# UART.net
KiCad netlist of a schematic drawn in Altium Designer
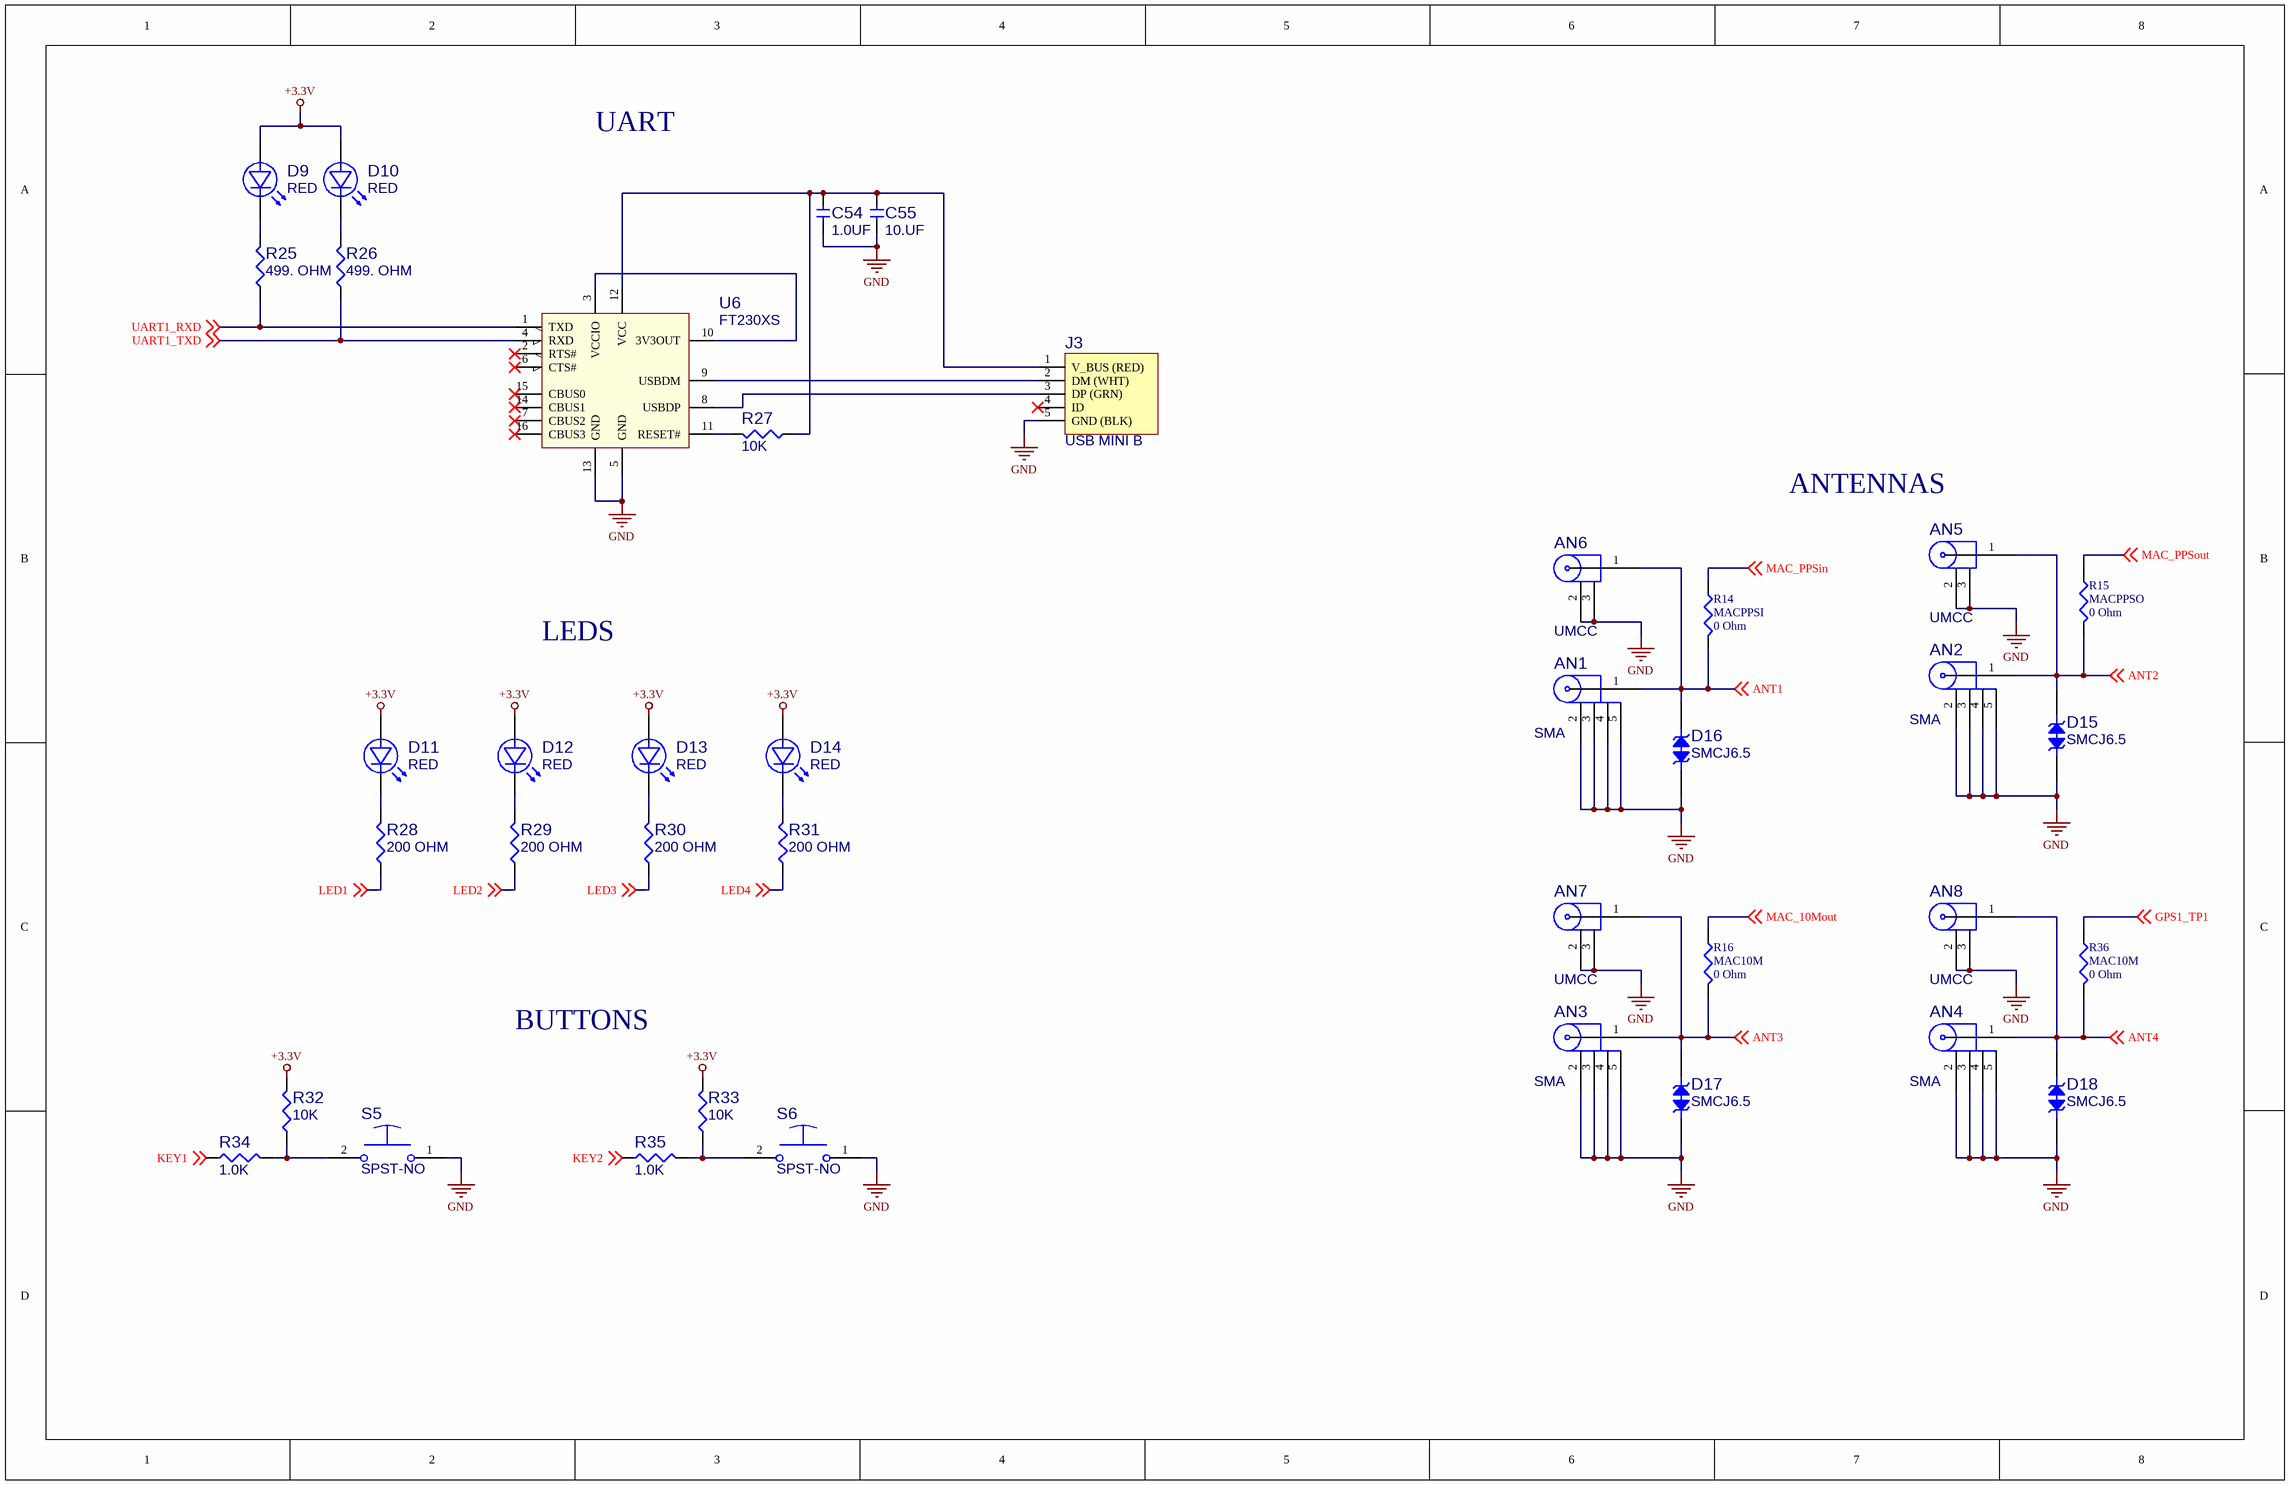
[diagram p0: UART.SchDoc]

(export (version "E")
  (design (tool "Eeschema 10.0.6"))
  (components
    (comp (ref "AN1")
      (value "SMA")
      (footprint "AMPHENOL-901-143-6RFX")
      (description "CONN, JACK, SMA, FEMALE, 50 OHM, R/A, GOLD, TH")
      (fields (field (name "MFG PART NUM") "901-143-6RFX") (field (name "VALENTIUM PART NUM") "<VALENTIUM>"))
      (libsource (lib "Connectors") (part "RF-901-143-6FRX"))
    )
    (comp (ref "AN2")
      (value "SMA")
      (footprint "AMPHENOL-901-143-6RFX")
      (description "CONN, JACK, SMA, FEMALE, 50 OHM, R/A, GOLD, TH")
      (fields (field (name "MFG PART NUM") "901-143-6RFX") (field (name "VALENTIUM PART NUM") "<VALENTIUM>"))
      (libsource (lib "Connectors") (part "RF-901-143-6FRX"))
    )
    (comp (ref "AN3")
      (value "SMA")
      (footprint "AMPHENOL-901-143-6RFX")
      (description "CONN, JACK, SMA, FEMALE, 50 OHM, R/A, GOLD, TH")
      (fields (field (name "MFG PART NUM") "901-143-6RFX") (field (name "VALENTIUM PART NUM") "<VALENTIUM>"))
      (libsource (lib "Connectors") (part "RF-901-143-6FRX"))
    )
    (comp (ref "AN4")
      (value "SMA")
      (footprint "AMPHENOL-901-143-6RFX")
      (description "CONN, JACK, SMA, FEMALE, 50 OHM, R/A, GOLD, TH")
      (fields (field (name "MFG PART NUM") "901-143-6RFX") (field (name "VALENTIUM PART NUM") "<VALENTIUM>"))
      (libsource (lib "Connectors") (part "RF-901-143-6FRX"))
    )
    (comp (ref "AN5")
      (value "UMCC")
      (footprint "U.FL UMCC JACK")
      (description "CONN, JACK, UMCC, MALE, 50 OHM, U.FL, GOLD, SMT")
      (fields (field (name "MFG PART NUM") "1909763-1") (field (name "VALENTIUM PART NUM") "<VALENTIUM>"))
      (libsource (lib "Connectors") (part "UMCC"))
    )
    (comp (ref "AN6")
      (value "UMCC")
      (footprint "U.FL UMCC JACK")
      (description "CONN, JACK, UMCC, MALE, 50 OHM, U.FL, GOLD, SMT")
      (fields (field (name "MFG PART NUM") "1909763-1") (field (name "VALENTIUM PART NUM") "<VALENTIUM>"))
      (libsource (lib "Connectors") (part "UMCC"))
    )
    (comp (ref "AN7")
      (value "UMCC")
      (footprint "U.FL UMCC JACK")
      (description "CONN, JACK, UMCC, MALE, 50 OHM, U.FL, GOLD, SMT")
      (fields (field (name "MFG PART NUM") "1909763-1") (field (name "VALENTIUM PART NUM") "<VALENTIUM>"))
      (libsource (lib "Connectors") (part "UMCC"))
    )
    (comp (ref "AN8")
      (value "UMCC")
      (footprint "U.FL UMCC JACK")
      (description "CONN, JACK, UMCC, MALE, 50 OHM, U.FL, GOLD, SMT")
      (fields (field (name "MFG PART NUM") "1909763-1") (field (name "VALENTIUM PART NUM") "<VALENTIUM>"))
      (libsource (lib "Connectors") (part "UMCC"))
    )
    (comp (ref "C54")
      (value "1.0UF")
      (footprint "CAPC2012X14N")
      (description "CAP, CER, 1.0UF, 25V, 10%, X5R, 0805")
      (fields
        (field (name "MFG PART NUM") "08053D105KAT2A")
        (field (name "VALENTIUM PART NUM") "<VALENTIUM>")
      )
      (libsource (lib "Capacitors") (part "CAP_0805_1UF_25V"))
    )
    (comp (ref "C55")
      (value "10.UF")
      (footprint "CAPC1608X10N")
      (description "CAP, CER, 10.UF, 25V, 20%, X5R, AEC-Q200, 0603")
      (fields
        (field (name "MFG PART NUM") "GRT188R61E106ME13D")
        (field (name "VALENTIUM PART NUM") "<VALENTIUM>")
      )
      (libsource (lib "Capacitors") (part "CAP_0603_10UF_25V"))
    )
    (comp (ref "D9")
      (value "RED")
      (footprint "DIOM1608X06N")
      (description "LED, RED, SML-LX0603, 635NM, 2V, 20MA, 0603")
      (fields
        (field (name "MFG PART NUM") "SML-LX0603IW-TR")
        (field (name "VALENTIUM PART NUM") "<VALENTIUM>")
      )
      (libsource (lib "Passives") (part "SMTLED_RED_0603_SML"))
    )
    (comp (ref "D10")
      (value "RED")
      (footprint "DIOM1608X06N")
      (description "LED, RED, SML-LX0603, 635NM, 2V, 20MA, 0603")
      (fields
        (field (name "MFG PART NUM") "SML-LX0603IW-TR")
        (field (name "VALENTIUM PART NUM") "<VALENTIUM>")
      )
      (libsource (lib "Passives") (part "SMTLED_RED_0603_SML"))
    )
    (comp (ref "D11")
      (value "RED")
      (footprint "DIOM1608X06N")
      (description "LED, RED, SML-LX0603, 635NM, 2V, 20MA, 0603")
      (fields
        (field (name "MFG PART NUM") "SML-LX0603IW-TR")
        (field (name "VALENTIUM PART NUM") "<VALENTIUM>")
      )
      (libsource (lib "Passives") (part "SMTLED_RED_0603_SML"))
    )
    (comp (ref "D12")
      (value "RED")
      (footprint "DIOM1608X06N")
      (description "LED, RED, SML-LX0603, 635NM, 2V, 20MA, 0603")
      (fields
        (field (name "MFG PART NUM") "SML-LX0603IW-TR")
        (field (name "VALENTIUM PART NUM") "<VALENTIUM>")
      )
      (libsource (lib "Passives") (part "SMTLED_RED_0603_SML"))
    )
    (comp (ref "D13")
      (value "RED")
      (footprint "DIOM1608X06N")
      (description "LED, RED, SML-LX0603, 635NM, 2V, 20MA, 0603")
      (fields
        (field (name "MFG PART NUM") "SML-LX0603IW-TR")
        (field (name "VALENTIUM PART NUM") "<VALENTIUM>")
      )
      (libsource (lib "Passives") (part "SMTLED_RED_0603_SML"))
    )
    (comp (ref "D14")
      (value "RED")
      (footprint "DIOM1608X06N")
      (description "LED, RED, SML-LX0603, 635NM, 2V, 20MA, 0603")
      (fields
        (field (name "MFG PART NUM") "SML-LX0603IW-TR")
        (field (name "VALENTIUM PART NUM") "<VALENTIUM>")
      )
      (libsource (lib "Passives") (part "SMTLED_RED_0603_SML"))
    )
    (comp (ref "D15")
      (value "SMCJ6.5")
      (footprint "DIOM6959X26N")
      (description "DIO, TVS, SMCJ6.5, 6.5V, BIDIR, 1.5KW, SMC")
      (fields (field (name "MFG PART NUM") "SMCJ6.5CA") (field (name "VALENTIUM PART NUM") "<VALENTIUM>"))
      (libsource (lib "Passives") (part "SMCJ6.5CA"))
    )
    (comp (ref "D16")
      (value "SMCJ6.5")
      (footprint "DIOM6959X26N")
      (description "DIO, TVS, SMCJ6.5, 6.5V, BIDIR, 1.5KW, SMC")
      (fields (field (name "MFG PART NUM") "SMCJ6.5CA") (field (name "VALENTIUM PART NUM") "<VALENTIUM>"))
      (libsource (lib "Passives") (part "SMCJ6.5CA"))
    )
    (comp (ref "D17")
      (value "SMCJ6.5")
      (footprint "DIOM6959X26N")
      (description "DIO, TVS, SMCJ6.5, 6.5V, BIDIR, 1.5KW, SMC")
      (fields (field (name "MFG PART NUM") "SMCJ6.5CA") (field (name "VALENTIUM PART NUM") "<VALENTIUM>"))
      (libsource (lib "Passives") (part "SMCJ6.5CA"))
    )
    (comp (ref "D18")
      (value "SMCJ6.5")
      (footprint "DIOM6959X26N")
      (description "DIO, TVS, SMCJ6.5, 6.5V, BIDIR, 1.5KW, SMC")
      (fields (field (name "MFG PART NUM") "SMCJ6.5CA") (field (name "VALENTIUM PART NUM") "<VALENTIUM>"))
      (libsource (lib "Passives") (part "SMCJ6.5CA"))
    )
    (comp (ref "J3")
      (value "USB MINI B")
      (footprint "USB_1734035")
      (description "CONN, REC, USB, R/A, MINI, TYPE B, 5 POS, SMT W/BRD GUIDE")
      (fields (field (name "MFG PART NUM") "1734035-2") (field (name "VALENTIUM PART NUM") "<VALENTIUM>"))
      (libsource (lib "Connectors") (part "USB_B_1734035"))
    )
    (comp (ref "R14")
      (value "MACPPSI")
      (footprint "J1-0603")
      (description "Resistor")
      (fields (field (name "ALTIUM_VALUE") "0 Ohm") (field (name "PUBLISHER") "Altium Limited"))
      (libsource (lib "Miscellaneous Devices") (part "Res3"))
    )
    (comp (ref "R15")
      (value "MACPPSO")
      (footprint "J1-0603")
      (description "Resistor")
      (fields (field (name "ALTIUM_VALUE") "0 Ohm") (field (name "PUBLISHER") "Altium Limited"))
      (libsource (lib "Miscellaneous Devices") (part "Res3"))
    )
    (comp (ref "R16")
      (value "MAC10M")
      (footprint "J1-0603")
      (description "Resistor")
      (fields (field (name "ALTIUM_VALUE") "0 Ohm") (field (name "PUBLISHER") "Altium Limited"))
      (libsource (lib "Miscellaneous Devices") (part "Res3"))
    )
    (comp (ref "R25")
      (value "499. OHM")
      (footprint "RESC1005X04N")
      (description "RES, 499. OHM, 1%, 1/16W, TF, AEC-Q200, 0402")
      (fields (field (name "MFG PART NUM") "ERJ-2RKF4990X") (field (name "VELENTIUM PART NUM") "<VELENTIUM>"))
      (libsource (lib "Resistors") (part "RES_0402_499"))
    )
    (comp (ref "R26")
      (value "499. OHM")
      (footprint "RESC1005X04N")
      (description "RES, 499. OHM, 1%, 1/16W, TF, AEC-Q200, 0402")
      (fields (field (name "MFG PART NUM") "ERJ-2RKF4990X") (field (name "VELENTIUM PART NUM") "<VELENTIUM>"))
      (libsource (lib "Resistors") (part "RES_0402_499"))
    )
    (comp (ref "R27")
      (value "10K")
      (footprint "RESC1608X50N")
      (description "RES, 10K, 1%, 1/10W, TF, 0603")
      (fields (field (name "MFG PART NUM") "ERJ-3EKF1002V") (field (name "VELENTIUM PART NUM") "<VELENTIUM>"))
      (libsource (lib "Resistors") (part "RES_0603_10K"))
    )
    (comp (ref "R28")
      (value "200 OHM")
      (footprint "RESC1608X50N")
      (description "RES, 200 OHM, 1%, 1/10W, TF, 0603")
      (fields (field (name "MFG PART NUM") "ERJ-3EKF2000V") (field (name "VELENTIUM PART NUM") "<VELENTIUM>"))
      (libsource (lib "Resistors") (part "RES_0603_200"))
    )
    (comp (ref "R29")
      (value "200 OHM")
      (footprint "RESC1608X50N")
      (description "RES, 200 OHM, 1%, 1/10W, TF, 0603")
      (fields (field (name "MFG PART NUM") "ERJ-3EKF2000V") (field (name "VELENTIUM PART NUM") "<VELENTIUM>"))
      (libsource (lib "Resistors") (part "RES_0603_200"))
    )
    (comp (ref "R30")
      (value "200 OHM")
      (footprint "RESC1608X50N")
      (description "RES, 200 OHM, 1%, 1/10W, TF, 0603")
      (fields (field (name "MFG PART NUM") "ERJ-3EKF2000V") (field (name "VELENTIUM PART NUM") "<VELENTIUM>"))
      (libsource (lib "Resistors") (part "RES_0603_200"))
    )
    (comp (ref "R31")
      (value "200 OHM")
      (footprint "RESC1608X50N")
      (description "RES, 200 OHM, 1%, 1/10W, TF, 0603")
      (fields (field (name "MFG PART NUM") "ERJ-3EKF2000V") (field (name "VELENTIUM PART NUM") "<VELENTIUM>"))
      (libsource (lib "Resistors") (part "RES_0603_200"))
    )
    (comp (ref "R32")
      (value "10K")
      (footprint "RESC1608X50N")
      (description "RES, 10K, 1%, 1/10W, TF, 0603")
      (fields (field (name "MFG PART NUM") "ERJ-3EKF1002V") (field (name "VELENTIUM PART NUM") "<VELENTIUM>"))
      (libsource (lib "Resistors") (part "RES_0603_10K"))
    )
    (comp (ref "R33")
      (value "10K")
      (footprint "RESC1608X50N")
      (description "RES, 10K, 1%, 1/10W, TF, 0603")
      (fields (field (name "MFG PART NUM") "ERJ-3EKF1002V") (field (name "VELENTIUM PART NUM") "<VELENTIUM>"))
      (libsource (lib "Resistors") (part "RES_0603_10K"))
    )
    (comp (ref "R34")
      (value "1.0K")
      (footprint "RESC1608X50N")
      (description "RES, 1.0K, 1%, 1/10W, TF, 0603")
      (fields (field (name "MFG PART NUM") "ERJ-3EKF1001V") (field (name "VELENTIUM PART NUM") "<VELENTIUM>"))
      (libsource (lib "Resistors") (part "RES_0603_1.0K"))
    )
    (comp (ref "R35")
      (value "1.0K")
      (footprint "RESC1608X50N")
      (description "RES, 1.0K, 1%, 1/10W, TF, 0603")
      (fields (field (name "MFG PART NUM") "ERJ-3EKF1001V") (field (name "VELENTIUM PART NUM") "<VELENTIUM>"))
      (libsource (lib "Resistors") (part "RES_0603_1.0K"))
    )
    (comp (ref "R36")
      (value "MAC10M")
      (footprint "J1-0603")
      (description "Resistor")
      (fields (field (name "ALTIUM_VALUE") "0 Ohm") (field (name "PUBLISHER") "Altium Limited"))
      (libsource (lib "Miscellaneous Devices") (part "Res3"))
    )
    (comp (ref "S5")
      (value "SPST-NO")
      (footprint "OMRON-B3U-1000P")
      (description "SW, SPST-NO, TACT, 12V, 50MA, 3X2.5MM SMT, B3U SERIES")
      (fields (field (name "MFG PART NUM") "B3U-1000P") (field (name "VALENTIUM PART NUM") "<VALENTIUM>"))
      (libsource (lib "Miscellaneous") (part "B3U-1000P"))
    )
    (comp (ref "S6")
      (value "SPST-NO")
      (footprint "OMRON-B3U-1000P")
      (description "SW, SPST-NO, TACT, 12V, 50MA, 3X2.5MM SMT, B3U SERIES")
      (fields (field (name "MFG PART NUM") "B3U-1000P") (field (name "VALENTIUM PART NUM") "<VALENTIUM>"))
      (libsource (lib "Miscellaneous") (part "B3U-1000P"))
    )
    (comp (ref "U6")
      (value "FT230XS")
      (footprint "SOP64P600X170-16N")
      (description "IC, TCVR, FT230, USB TO UART, 5V, FTDI, 16SSOP")
      (fields (field (name "MFG PART NUM") "FT230XS-R") (field (name "VELENTIUM PART NUM") "<V PART NUM>"))
      (libsource (lib "IntegratedCircuits") (part "FT230XS-R"))
    )
  )
  (nets
    (net (code "1") (name "+3.3V") (class "Default")
      (node (ref "D10") (pin "2") (pinfunction "A_2") (pintype "passive"))
      (node (ref "D11") (pin "2") (pinfunction "A_2") (pintype "passive"))
      (node (ref "D12") (pin "2") (pinfunction "A_2") (pintype "passive"))
      (node (ref "D13") (pin "2") (pinfunction "A_2") (pintype "passive"))
      (node (ref "D14") (pin "2") (pinfunction "A_2") (pintype "passive"))
      (node (ref "D9") (pin "2") (pinfunction "A_2") (pintype "passive"))
      (node (ref "R32") (pin "2") (pinfunction "2_2") (pintype "passive"))
      (node (ref "R33") (pin "2") (pinfunction "2_2") (pintype "passive"))
    )
    (net (code "2") (name "ANT1") (class "Default")
      (node (ref "AN1") (pin "1") (pinfunction "1_1") (pintype "passive"))
      (node (ref "AN6") (pin "1") (pinfunction "1_1") (pintype "passive"))
      (node (ref "D16") (pin "A") (pinfunction "A_A") (pintype "passive"))
      (node (ref "R14") (pin "2") (pinfunction "2_2") (pintype "passive"))
    )
    (net (code "3") (name "ANT2") (class "Default")
      (node (ref "AN2") (pin "1") (pinfunction "1_1") (pintype "passive"))
      (node (ref "AN5") (pin "1") (pinfunction "1_1") (pintype "passive"))
      (node (ref "D15") (pin "A") (pinfunction "A_A") (pintype "passive"))
      (node (ref "R15") (pin "2") (pinfunction "2_2") (pintype "passive"))
    )
    (net (code "4") (name "ANT3") (class "Default")
      (node (ref "AN3") (pin "1") (pinfunction "1_1") (pintype "passive"))
      (node (ref "AN7") (pin "1") (pinfunction "1_1") (pintype "passive"))
      (node (ref "D17") (pin "A") (pinfunction "A_A") (pintype "passive"))
      (node (ref "R16") (pin "2") (pinfunction "2_2") (pintype "passive"))
    )
    (net (code "5") (name "ANT4") (class "Default")
      (node (ref "AN4") (pin "1") (pinfunction "1_1") (pintype "passive"))
      (node (ref "AN8") (pin "1") (pinfunction "1_1") (pintype "passive"))
      (node (ref "D18") (pin "A") (pinfunction "A_A") (pintype "passive"))
      (node (ref "R36") (pin "2") (pinfunction "2_2") (pintype "passive"))
    )
    (net (code "6") (name "GND") (class "Default")
      (node (ref "AN1") (pin "2") (pinfunction "2_2") (pintype "passive"))
      (node (ref "AN1") (pin "3") (pinfunction "3_3") (pintype "passive"))
      (node (ref "AN1") (pin "4") (pinfunction "4_4") (pintype "passive"))
      (node (ref "AN1") (pin "5") (pinfunction "5_5") (pintype "passive"))
      (node (ref "AN2") (pin "2") (pinfunction "2_2") (pintype "passive"))
      (node (ref "AN2") (pin "3") (pinfunction "3_3") (pintype "passive"))
      (node (ref "AN2") (pin "4") (pinfunction "4_4") (pintype "passive"))
      (node (ref "AN2") (pin "5") (pinfunction "5_5") (pintype "passive"))
      (node (ref "AN3") (pin "2") (pinfunction "2_2") (pintype "passive"))
      (node (ref "AN3") (pin "3") (pinfunction "3_3") (pintype "passive"))
      (node (ref "AN3") (pin "4") (pinfunction "4_4") (pintype "passive"))
      (node (ref "AN3") (pin "5") (pinfunction "5_5") (pintype "passive"))
      (node (ref "AN4") (pin "2") (pinfunction "2_2") (pintype "passive"))
      (node (ref "AN4") (pin "3") (pinfunction "3_3") (pintype "passive"))
      (node (ref "AN4") (pin "4") (pinfunction "4_4") (pintype "passive"))
      (node (ref "AN4") (pin "5") (pinfunction "5_5") (pintype "passive"))
      (node (ref "AN5") (pin "2") (pinfunction "2_2") (pintype "passive"))
      (node (ref "AN5") (pin "3") (pinfunction "3_3") (pintype "passive"))
      (node (ref "AN6") (pin "2") (pinfunction "2_2") (pintype "passive"))
      (node (ref "AN6") (pin "3") (pinfunction "3_3") (pintype "passive"))
      (node (ref "AN7") (pin "2") (pinfunction "2_2") (pintype "passive"))
      (node (ref "AN7") (pin "3") (pinfunction "3_3") (pintype "passive"))
      (node (ref "AN8") (pin "2") (pinfunction "2_2") (pintype "passive"))
      (node (ref "AN8") (pin "3") (pinfunction "3_3") (pintype "passive"))
      (node (ref "C54") (pin "1") (pinfunction "1_1") (pintype "passive"))
      (node (ref "C55") (pin "1") (pinfunction "1_1") (pintype "passive"))
      (node (ref "D15") (pin "K") (pinfunction "K_K") (pintype "passive"))
      (node (ref "D16") (pin "K") (pinfunction "K_K") (pintype "passive"))
      (node (ref "D17") (pin "K") (pinfunction "K_K") (pintype "passive"))
      (node (ref "D18") (pin "K") (pinfunction "K_K") (pintype "passive"))
      (node (ref "J3") (pin "5") (pinfunction "GND_(BLK)_5") (pintype "passive"))
      (node (ref "S5") (pin "1") (pintype "passive"))
      (node (ref "S6") (pin "1") (pintype "passive"))
      (node (ref "U6") (pin "13") (pinfunction "GND_13") (pintype "passive"))
      (node (ref "U6") (pin "5") (pinfunction "GND_5") (pintype "passive"))
    )
    (net (code "7") (name "GPS1_TP1") (class "Default")
      (node (ref "R36") (pin "1") (pinfunction "1_1") (pintype "passive"))
    )
    (net (code "8") (name "KEY1") (class "Default")
      (node (ref "R34") (pin "1") (pinfunction "1_1") (pintype "passive"))
    )
    (net (code "9") (name "KEY2") (class "Default")
      (node (ref "R35") (pin "1") (pinfunction "1_1") (pintype "passive"))
    )
    (net (code "10") (name "LED1") (class "Default")
      (node (ref "R28") (pin "1") (pinfunction "1_1") (pintype "passive"))
    )
    (net (code "11") (name "LED2") (class "Default")
      (node (ref "R29") (pin "1") (pinfunction "1_1") (pintype "passive"))
    )
    (net (code "12") (name "LED3") (class "Default")
      (node (ref "R30") (pin "1") (pinfunction "1_1") (pintype "passive"))
    )
    (net (code "13") (name "LED4") (class "Default")
      (node (ref "R31") (pin "1") (pinfunction "1_1") (pintype "passive"))
    )
    (net (code "14") (name "MAC_10Mout") (class "Default")
      (node (ref "R16") (pin "1") (pinfunction "1_1") (pintype "passive"))
    )
    (net (code "15") (name "MAC_PPSin") (class "Default")
      (node (ref "R14") (pin "1") (pinfunction "1_1") (pintype "passive"))
    )
    (net (code "16") (name "MAC_PPSout") (class "Default")
      (node (ref "R15") (pin "1") (pinfunction "1_1") (pintype "passive"))
    )
    (net (code "17") (name "Net-(D9-K)") (class "Default")
      (node (ref "D9") (pin "1") (pinfunction "K_1") (pintype "passive"))
      (node (ref "R25") (pin "2") (pinfunction "2_2") (pintype "passive"))
    )
    (net (code "18") (name "Net-(D10-K)") (class "Default")
      (node (ref "D10") (pin "1") (pinfunction "K_1") (pintype "passive"))
      (node (ref "R26") (pin "2") (pinfunction "2_2") (pintype "passive"))
    )
    (net (code "19") (name "Net-(D11-K)") (class "Default")
      (node (ref "D11") (pin "1") (pinfunction "K_1") (pintype "passive"))
      (node (ref "R28") (pin "2") (pinfunction "2_2") (pintype "passive"))
    )
    (net (code "20") (name "Net-(D12-K)") (class "Default")
      (node (ref "D12") (pin "1") (pinfunction "K_1") (pintype "passive"))
      (node (ref "R29") (pin "2") (pinfunction "2_2") (pintype "passive"))
    )
    (net (code "21") (name "Net-(D13-K)") (class "Default")
      (node (ref "D13") (pin "1") (pinfunction "K_1") (pintype "passive"))
      (node (ref "R30") (pin "2") (pinfunction "2_2") (pintype "passive"))
    )
    (net (code "22") (name "Net-(D14-K)") (class "Default")
      (node (ref "D14") (pin "1") (pinfunction "K_1") (pintype "passive"))
      (node (ref "R31") (pin "2") (pinfunction "2_2") (pintype "passive"))
    )
    (net (code "23") (name "Net-(J3-DM_(WHT))") (class "Default")
      (node (ref "J3") (pin "2") (pinfunction "DM_(WHT)_2") (pintype "passive"))
      (node (ref "U6") (pin "9") (pinfunction "USBDM_9") (pintype "passive"))
    )
    (net (code "24") (name "Net-(J3-DP_(GRN))") (class "Default")
      (node (ref "J3") (pin "3") (pinfunction "DP_(GRN)_3") (pintype "passive"))
      (node (ref "U6") (pin "8") (pinfunction "USBDP_8") (pintype "passive"))
    )
    (net (code "25") (name "Net-(J3-V_BUS_(RED))") (class "Default")
      (node (ref "C54") (pin "2") (pinfunction "2_2") (pintype "passive"))
      (node (ref "C55") (pin "2") (pinfunction "2_2") (pintype "passive"))
      (node (ref "J3") (pin "1") (pinfunction "V_BUS_(RED)_1") (pintype "passive"))
      (node (ref "R27") (pin "1") (pinfunction "1_1") (pintype "passive"))
      (node (ref "U6") (pin "12") (pinfunction "VCC_12") (pintype "passive"))
    )
    (net (code "26") (name "Net-(R32-Pad1)") (class "Default")
      (node (ref "R32") (pin "1") (pinfunction "1_1") (pintype "passive"))
      (node (ref "R34") (pin "2") (pinfunction "2_2") (pintype "passive"))
      (node (ref "S5") (pin "2") (pintype "passive"))
    )
    (net (code "27") (name "Net-(R33-Pad1)") (class "Default")
      (node (ref "R33") (pin "1") (pinfunction "1_1") (pintype "passive"))
      (node (ref "R35") (pin "2") (pinfunction "2_2") (pintype "passive"))
      (node (ref "S6") (pin "2") (pintype "passive"))
    )
    (net (code "28") (name "Net-(U6-3V3OUT)") (class "Default")
      (node (ref "U6") (pin "10") (pinfunction "3V3OUT_10") (pintype "passive"))
      (node (ref "U6") (pin "3") (pinfunction "VCCIO_3") (pintype "passive"))
    )
    (net (code "29") (name "Net-(U6-RESET#)") (class "Default")
      (node (ref "R27") (pin "2") (pinfunction "2_2") (pintype "passive"))
      (node (ref "U6") (pin "11") (pinfunction "RESET#_11") (pintype "passive"))
    )
    (net (code "30") (name "UART1_RXD") (class "Default")
      (node (ref "R25") (pin "1") (pinfunction "1_1") (pintype "passive"))
      (node (ref "U6") (pin "1") (pinfunction "TXD_1") (pintype "passive"))
    )
    (net (code "31") (name "UART1_TXD") (class "Default")
      (node (ref "R26") (pin "1") (pinfunction "1_1") (pintype "passive"))
      (node (ref "U6") (pin "4") (pinfunction "RXD_4") (pintype "passive"))
    )
    (net (code "32") (name "unconnected-(J3-ID-Pad4)") (class "Default")
      (node (ref "J3") (pin "4") (pinfunction "ID_4") (pintype "passive+no_connect"))
    )
    (net (code "33") (name "unconnected-(U6-CBUS0-Pad15)") (class "Default")
      (node (ref "U6") (pin "15") (pinfunction "CBUS0_15") (pintype "passive+no_connect"))
    )
    (net (code "34") (name "unconnected-(U6-CBUS1-Pad14)") (class "Default")
      (node (ref "U6") (pin "14") (pinfunction "CBUS1_14") (pintype "passive+no_connect"))
    )
    (net (code "35") (name "unconnected-(U6-CBUS2-Pad7)") (class "Default")
      (node (ref "U6") (pin "7") (pinfunction "CBUS2_7") (pintype "passive+no_connect"))
    )
    (net (code "36") (name "unconnected-(U6-CBUS3-Pad16)") (class "Default")
      (node (ref "U6") (pin "16") (pinfunction "CBUS3_16") (pintype "passive+no_connect"))
    )
    (net (code "37") (name "unconnected-(U6-CTS#-Pad6)") (class "Default")
      (node (ref "U6") (pin "6") (pinfunction "CTS#_6") (pintype "passive+no_connect"))
    )
    (net (code "38") (name "unconnected-(U6-RTS#-Pad2)") (class "Default")
      (node (ref "U6") (pin "2") (pinfunction "RTS#_2") (pintype "passive+no_connect"))
    )
  )
)
